# Meganrev_1.net
KiCad netlist of a schematic drawn in EAGLE
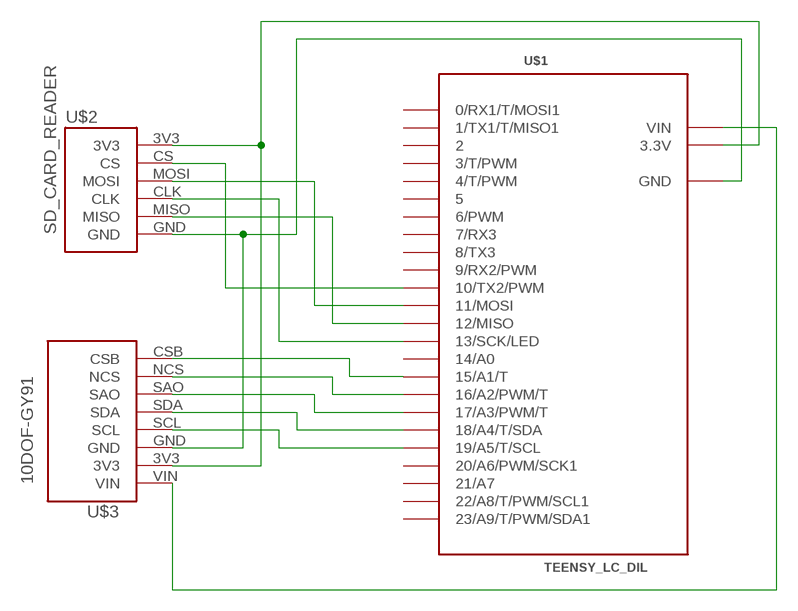
[diagram p0: schematic, sheet 1]

(export (version "E")
  (design (tool "Eeschema 10.0.6"))
  (components
    (comp (ref "U$1")
      (value "TEENSY_LC_DIL")
      (footprint "eagle-import:TEENSY_3.0-3.2&LC_DIL")
      (libsource (lib "eagle-import") (part "TEENSY_LC_DIL"))
    )
    (comp (ref "U$2")
      (value "SD_CARD_READER")
      (footprint "eagle-import:MICRO_SD_READER_3V3")
      (libsource (lib "eagle-import") (part "SD_CARD_READER"))
    )
    (comp (ref "U$3")
      (value "10DOF-GY91")
      (footprint "eagle-import:10DOF-GY-91")
      (libsource (lib "eagle-import") (part "10DOF-GY91"))
    )
  )
  (nets
    (net (code "1") (name "Net-(U$1-10{slash}TX2{slash}PWM)") (class "Default")
      (node (ref "U$1") (pin "10") (pinfunction "10/TX2/PWM_10") (pintype "bidirectional"))
      (node (ref "U$2") (pin "CS") (pinfunction "CS_CS") (pintype "bidirectional"))
    )
    (net (code "2") (name "Net-(U$1-11{slash}MOSI)") (class "Default")
      (node (ref "U$1") (pin "11") (pinfunction "11/MOSI_11") (pintype "bidirectional"))
      (node (ref "U$2") (pin "MOSI") (pinfunction "MOSI_MOSI") (pintype "bidirectional"))
    )
    (net (code "3") (name "Net-(U$1-12{slash}MISO)") (class "Default")
      (node (ref "U$1") (pin "12") (pinfunction "12/MISO_12") (pintype "bidirectional"))
      (node (ref "U$2") (pin "MISO") (pinfunction "MISO_MISO") (pintype "bidirectional"))
    )
    (net (code "4") (name "Net-(U$1-13{slash}SCK{slash}LED)") (class "Default")
      (node (ref "U$1") (pin "13") (pinfunction "13/SCK/LED_13") (pintype "bidirectional"))
      (node (ref "U$2") (pin "CLK") (pinfunction "CLK_CLK") (pintype "bidirectional"))
    )
    (net (code "5") (name "Net-(U$1-15{slash}A1{slash}T)") (class "Default")
      (node (ref "U$1") (pin "15/A1") (pinfunction "15/A1/T_15/A1") (pintype "bidirectional"))
      (node (ref "U$3") (pin "CSB") (pinfunction "CSB_CSB") (pintype "bidirectional"))
    )
    (net (code "6") (name "Net-(U$1-16{slash}A2{slash}PWM{slash}T)") (class "Default")
      (node (ref "U$1") (pin "16/A2") (pinfunction "16/A2/PWM/T_16/A2") (pintype "bidirectional"))
      (node (ref "U$3") (pin "NCS") (pinfunction "NCS_NCS") (pintype "bidirectional"))
    )
    (net (code "7") (name "Net-(U$1-17{slash}A3{slash}PWM{slash}T)") (class "Default")
      (node (ref "U$1") (pin "17/A3") (pinfunction "17/A3/PWM/T_17/A3") (pintype "bidirectional"))
      (node (ref "U$3") (pin "SAO") (pinfunction "SAO_SAO") (pintype "bidirectional"))
    )
    (net (code "8") (name "Net-(U$1-18{slash}A4{slash}T{slash}SDA)") (class "Default")
      (node (ref "U$1") (pin "18/A4") (pinfunction "18/A4/T/SDA_18/A4") (pintype "bidirectional"))
      (node (ref "U$3") (pin "SDA") (pinfunction "SDA_SDA") (pintype "bidirectional"))
    )
    (net (code "9") (name "Net-(U$1-19{slash}A5{slash}T{slash}SCL)") (class "Default")
      (node (ref "U$1") (pin "19/A5") (pinfunction "19/A5/T/SCL_19/A5") (pintype "bidirectional"))
      (node (ref "U$3") (pin "SCL") (pinfunction "SCL_SCL") (pintype "bidirectional"))
    )
    (net (code "10") (name "Net-(U$1-GND-PadAGND)") (class "Default")
      (node (ref "U$1") (pin "AGND") (pinfunction "GND_AGND") (pintype "power_in"))
      (node (ref "U$1") (pin "GND") (pinfunction "GND_GND") (pintype "power_in"))
      (node (ref "U$2") (pin "GND") (pinfunction "GND_GND") (pintype "bidirectional"))
      (node (ref "U$3") (pin "GND") (pinfunction "GND_GND") (pintype "bidirectional"))
    )
    (net (code "11") (name "Net-(U$1-Pad3.3V)") (class "Default")
      (node (ref "U$1") (pin "3.3V") (pinfunction "3.3V_3.3V") (pintype "power_in"))
      (node (ref "U$2") (pin "3V3") (pinfunction "3V3_3V3") (pintype "bidirectional"))
      (node (ref "U$3") (pin "3V3") (pinfunction "3V3_3V3") (pintype "bidirectional"))
    )
    (net (code "12") (name "Net-(U$1-PadVIN)") (class "Default")
      (node (ref "U$1") (pin "VIN") (pinfunction "VIN_VIN") (pintype "power_in"))
      (node (ref "U$3") (pin "VIN") (pinfunction "VIN_VIN") (pintype "bidirectional"))
    )
    (net (code "13") (name "unconnected-(U$1-0{slash}RX1{slash}T{slash}MOSI1-Pad0)") (class "Default")
      (node (ref "U$1") (pin "0") (pinfunction "0/RX1/T/MOSI1_0") (pintype "bidirectional"))
    )
    (net (code "14") (name "unconnected-(U$1-1{slash}TX1{slash}T{slash}MISO1-Pad1)") (class "Default")
      (node (ref "U$1") (pin "1") (pinfunction "1/TX1/T/MISO1_1") (pintype "bidirectional"))
    )
    (net (code "15") (name "unconnected-(U$1-3{slash}T{slash}PWM-Pad3)") (class "Default")
      (node (ref "U$1") (pin "3") (pinfunction "3/T/PWM_3") (pintype "bidirectional"))
    )
    (net (code "16") (name "unconnected-(U$1-4{slash}T{slash}PWM-Pad4)") (class "Default")
      (node (ref "U$1") (pin "4") (pinfunction "4/T/PWM_4") (pintype "bidirectional"))
    )
    (net (code "17") (name "unconnected-(U$1-6{slash}PWM-Pad6)") (class "Default")
      (node (ref "U$1") (pin "6") (pinfunction "6/PWM_6") (pintype "bidirectional"))
    )
    (net (code "18") (name "unconnected-(U$1-7{slash}RX3-Pad7)") (class "Default")
      (node (ref "U$1") (pin "7") (pinfunction "7/RX3_7") (pintype "bidirectional"))
    )
    (net (code "19") (name "unconnected-(U$1-8{slash}TX3-Pad8)") (class "Default")
      (node (ref "U$1") (pin "8") (pinfunction "8/TX3_8") (pintype "bidirectional"))
    )
    (net (code "20") (name "unconnected-(U$1-9{slash}RX2{slash}PWM-Pad9)") (class "Default")
      (node (ref "U$1") (pin "9") (pinfunction "9/RX2/PWM_9") (pintype "bidirectional"))
    )
    (net (code "21") (name "unconnected-(U$1-20{slash}A6{slash}PWM{slash}SCK1-Pad20{slash}A6)") (class "Default")
      (node (ref "U$1") (pin "20/A6") (pinfunction "20/A6/PWM/SCK1_20/A6") (pintype "bidirectional"))
    )
    (net (code "22") (name "unconnected-(U$1-22{slash}A8{slash}T{slash}PWM{slash}SCL1-Pad22{slash}A8)") (class "Default")
      (node (ref "U$1") (pin "22/A8") (pinfunction "22/A8/T/PWM/SCL1_22/A8") (pintype "bidirectional"))
    )
    (net (code "23") (name "unconnected-(U$1-23{slash}A9{slash}T{slash}PWM{slash}SDA1-Pad23{slash}A9)") (class "Default")
      (node (ref "U$1") (pin "23/A9") (pinfunction "23/A9/T/PWM/SDA1_23/A9") (pintype "bidirectional"))
    )
    (net (code "24") (name "unconnected-(U$1-Pad2)") (class "Default")
      (node (ref "U$1") (pin "2") (pinfunction "2_2") (pintype "bidirectional"))
    )
    (net (code "25") (name "unconnected-(U$1-Pad5)") (class "Default")
      (node (ref "U$1") (pin "5") (pinfunction "5_5") (pintype "bidirectional"))
    )
    (net (code "26") (name "unconnected-(U$1-Pad14{slash}A0)") (class "Default")
      (node (ref "U$1") (pin "14/A0") (pinfunction "14/A0_14/A0") (pintype "bidirectional"))
    )
    (net (code "27") (name "unconnected-(U$1-Pad21{slash}A7)") (class "Default")
      (node (ref "U$1") (pin "21/A7") (pinfunction "21/A7_21/A7") (pintype "bidirectional"))
    )
  )
)
